# ZP_Force_Plates.net
KiCad netlist of a schematic drawn in Altium Designer
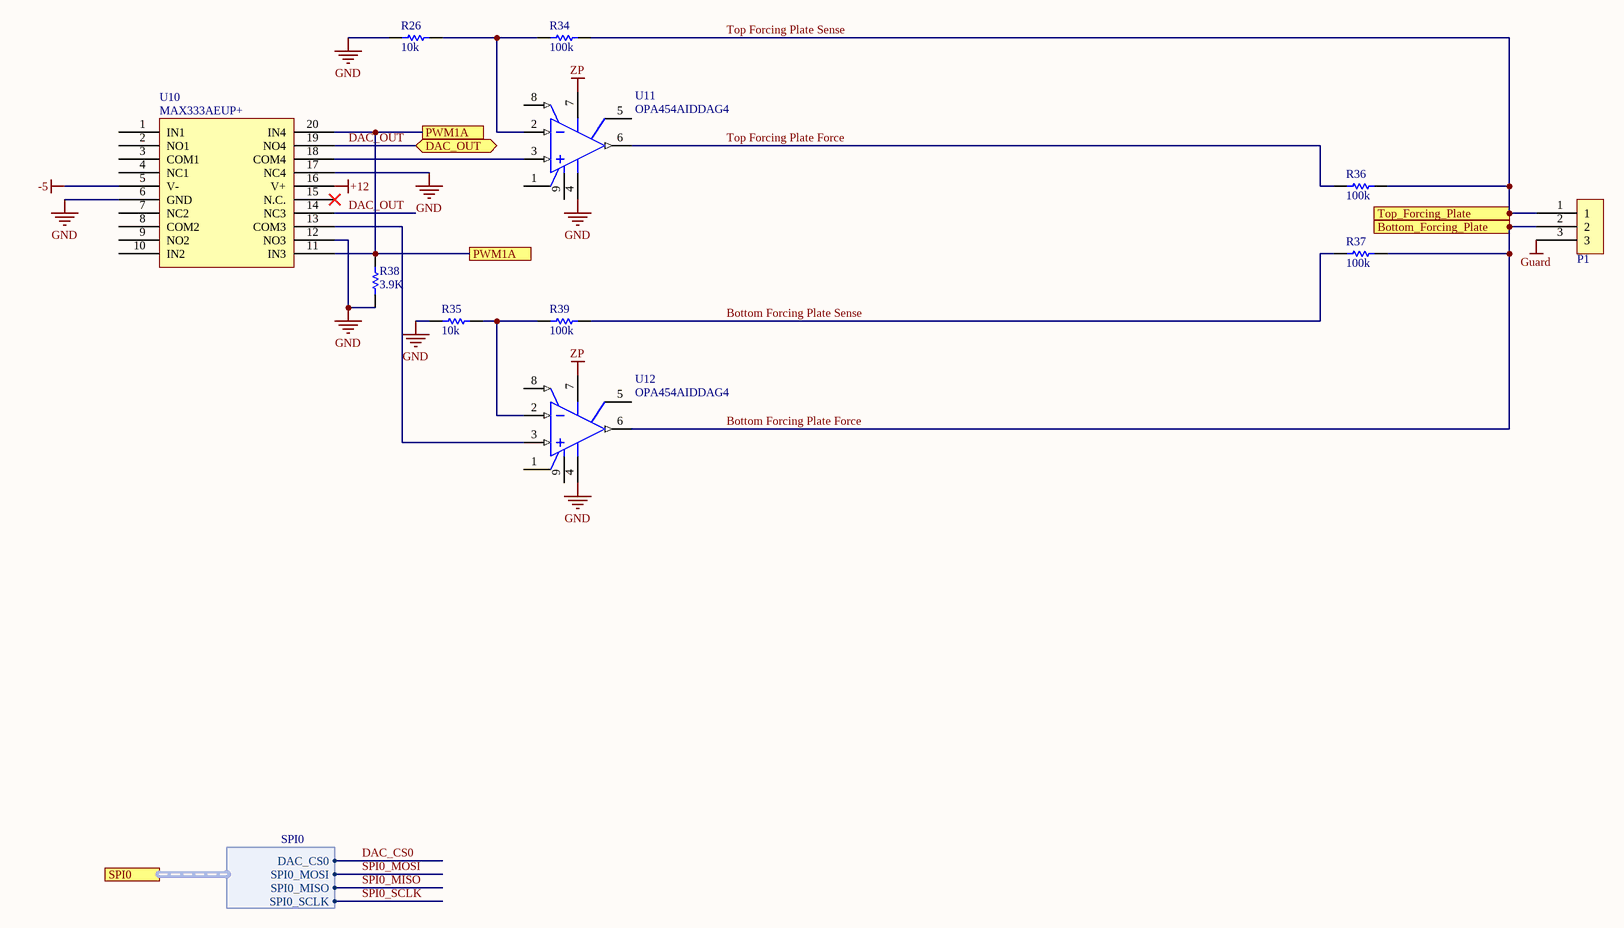
[diagram p0: ZP_Force_Plates.SchDoc]

(export (version "E")
  (design (tool "Eeschema 10.0.6"))
  (components
    (comp (ref "P1")
      (value "Triax_Conn")
      (footprint "Triax_Conn")
      (libsource (lib "ZLS_Schematic_lib") (part "Triax_Conn"))
    )
    (comp (ref "R26")
      (value "10k")
      (footprint "RESC0402(1005)_M")
      (libsource (lib "Altium Content Vault") (part "CMP-1011-00463-1"))
    )
    (comp (ref "R34")
      (value "100k")
      (footprint "RESC0402(1005)_M")
      (libsource (lib "Altium Content Vault") (part "CMP-1011-00463-1"))
    )
    (comp (ref "R35")
      (value "10k")
      (footprint "RESC0402(1005)_M")
      (libsource (lib "Altium Content Vault") (part "CMP-1011-00463-1"))
    )
    (comp (ref "R36")
      (value "100k")
      (footprint "RESC0402(1005)_M")
      (libsource (lib "Altium Content Vault") (part "CMP-1011-00651-1"))
    )
    (comp (ref "R37")
      (value "100k")
      (footprint "RESC0402(1005)_M")
      (libsource (lib "Altium Content Vault") (part "CMP-1011-00651-1"))
    )
    (comp (ref "R38")
      (value "3.9K")
      (footprint "RESC0402(1005)_M")
      (libsource (lib "Altium Content Vault") (part "CMP-1011-00463-1"))
    )
    (comp (ref "R39")
      (value "100k")
      (footprint "RESC0402(1005)_M")
      (libsource (lib "Altium Content Vault") (part "CMP-1011-00463-1"))
    )
    (comp (ref "U10")
      (value "MAX333AEUP+")
      (footprint "TSOP65P640X90-20N")
      (description "IC SWITCH QUAD SPDT 20TSSOP")
      (fields (field (name "MANUFACTURER") "Maxim Integrated") (field (name "BASE PART NUMBER") "MAX333"))
      (libsource (lib "ZLS_Schematic_lib") (part "MAX333CWP+"))
    )
    (comp (ref "U11")
      (value "OPA454AIDDAG4")
      (footprint "TI-DDA8-2745X2245TP_N")
      (fields (field (name "MANUFACTURER") "Texas Instruments"))
      (libsource (lib "Altium Content Vault") (part "TI-OPA454-DDA8"))
    )
    (comp (ref "U12")
      (value "OPA454AIDDAG4")
      (footprint "TI-DDA8-2745X2245TP_N")
      (fields (field (name "MANUFACTURER") "Texas Instruments"))
      (libsource (lib "Altium Content Vault") (part "TI-OPA454-DDA8"))
    )
  )
  (nets
    (net (code "2") (name "+12") (class "Default")
      (node (ref "U10") (pin "16") (pinfunction "V+_16") (pintype "power_in"))
    )
    (net (code "3") (name "-5") (class "Default")
      (node (ref "U10") (pin "5") (pinfunction "V-_5") (pintype "power_in"))
    )
    (net (code "4") (name "/Bottom Forcing Plate Force") (class "Default")
      (node (ref "P1") (pin "2") (pinfunction "2_2") (pintype "passive"))
      (node (ref "R37") (pin "1") (pinfunction "1_1") (pintype "passive"))
      (node (ref "U12") (pin "6") (pinfunction "OUT_6") (pintype "output"))
    )
    (net (code "5") (name "/Bottom Forcing Plate Sense") (class "Default")
      (node (ref "R37") (pin "2") (pinfunction "2_2") (pintype "passive"))
      (node (ref "R39") (pin "2") (pinfunction "2_2") (pintype "passive"))
    )
    (net (code "7") (name "/DAC_OUT") (class "Default")
      (node (ref "U10") (pin "14") (pinfunction "NC3_14") (pintype "passive"))
      (node (ref "U10") (pin "19") (pinfunction "NO4_19") (pintype "passive"))
    )
    (net (code "8") (name "/PWM1A") (class "Default")
      (node (ref "R38") (pin "2") (pinfunction "2_2") (pintype "passive"))
      (node (ref "U10") (pin "11") (pinfunction "IN3_11") (pintype "passive"))
      (node (ref "U10") (pin "20") (pinfunction "IN4_20") (pintype "passive"))
    )
    (net (code "12") (name "/Top Forcing Plate Force") (class "Default")
      (node (ref "R36") (pin "2") (pinfunction "2_2") (pintype "passive"))
      (node (ref "U11") (pin "6") (pinfunction "OUT_6") (pintype "output"))
    )
    (net (code "13") (name "/Top Forcing Plate Sense") (class "Default")
      (node (ref "P1") (pin "1") (pinfunction "1_1") (pintype "passive"))
      (node (ref "R34") (pin "2") (pinfunction "2_2") (pintype "passive"))
      (node (ref "R36") (pin "1") (pinfunction "1_1") (pintype "passive"))
    )
    (net (code "15") (name "GND") (class "Default")
      (node (ref "R26") (pin "1") (pinfunction "1_1") (pintype "passive"))
      (node (ref "R35") (pin "1") (pinfunction "1_1") (pintype "passive"))
      (node (ref "R38") (pin "1") (pinfunction "1_1") (pintype "passive"))
      (node (ref "U10") (pin "12") (pinfunction "NO3_12") (pintype "passive"))
      (node (ref "U10") (pin "17") (pinfunction "NC4_17") (pintype "passive"))
      (node (ref "U10") (pin "6") (pinfunction "GND_6") (pintype "passive"))
      (node (ref "U11") (pin "4") (pinfunction "V-_4") (pintype "power_in"))
      (node (ref "U12") (pin "4") (pinfunction "V-_4") (pintype "power_in"))
    )
    (net (code "16") (name "Guard") (class "Default")
      (node (ref "P1") (pin "3") (pinfunction "3_3") (pintype "passive"))
    )
    (net (code "17") (name "Net-(U10-COM3)") (class "Default")
      (node (ref "U10") (pin "13") (pinfunction "COM3_13") (pintype "passive"))
      (node (ref "U12") (pin "3") (pinfunction "IN+_3") (pintype "input"))
    )
    (net (code "18") (name "Net-(U10-COM4)") (class "Default")
      (node (ref "U10") (pin "18") (pinfunction "COM4_18") (pintype "passive"))
      (node (ref "U11") (pin "3") (pinfunction "IN+_3") (pintype "input"))
    )
    (net (code "19") (name "Net-(U11-IN-)") (class "Default")
      (node (ref "R26") (pin "2") (pinfunction "2_2") (pintype "passive"))
      (node (ref "R34") (pin "1") (pinfunction "1_1") (pintype "passive"))
      (node (ref "U11") (pin "2") (pinfunction "IN-_2") (pintype "input"))
    )
    (net (code "20") (name "Net-(U12-IN-)") (class "Default")
      (node (ref "R35") (pin "2") (pinfunction "2_2") (pintype "passive"))
      (node (ref "R39") (pin "1") (pinfunction "1_1") (pintype "passive"))
      (node (ref "U12") (pin "2") (pinfunction "IN-_2") (pintype "input"))
    )
    (net (code "21") (name "ZP") (class "Default")
      (node (ref "U11") (pin "7") (pinfunction "V+_7") (pintype "power_in"))
      (node (ref "U12") (pin "7") (pinfunction "V+_7") (pintype "power_in"))
    )
    (net (code "22") (name "unconnected-(U10-COM1-Pad3)") (class "Default")
      (node (ref "U10") (pin "3") (pinfunction "COM1_3") (pintype "passive"))
    )
    (net (code "23") (name "unconnected-(U10-COM2-Pad8)") (class "Default")
      (node (ref "U10") (pin "8") (pinfunction "COM2_8") (pintype "passive"))
    )
    (net (code "24") (name "unconnected-(U10-IN1-Pad1)") (class "Default")
      (node (ref "U10") (pin "1") (pinfunction "IN1_1") (pintype "passive"))
    )
    (net (code "25") (name "unconnected-(U10-IN2-Pad10)") (class "Default")
      (node (ref "U10") (pin "10") (pinfunction "IN2_10") (pintype "passive"))
    )
    (net (code "26") (name "unconnected-(U10-N.C.-Pad15)") (class "Default")
      (node (ref "U10") (pin "15") (pinfunction "N.C._15") (pintype "passive+no_connect"))
    )
    (net (code "27") (name "unconnected-(U10-NC1-Pad4)") (class "Default")
      (node (ref "U10") (pin "4") (pinfunction "NC1_4") (pintype "passive"))
    )
    (net (code "28") (name "unconnected-(U10-NC2-Pad7)") (class "Default")
      (node (ref "U10") (pin "7") (pinfunction "NC2_7") (pintype "passive"))
    )
    (net (code "29") (name "unconnected-(U10-NO1-Pad2)") (class "Default")
      (node (ref "U10") (pin "2") (pinfunction "NO1_2") (pintype "passive"))
    )
    (net (code "30") (name "unconnected-(U10-NO2-Pad9)") (class "Default")
      (node (ref "U10") (pin "9") (pinfunction "NO2_9") (pintype "passive"))
    )
    (net (code "31") (name "unconnected-(U11-EP-Pad9)") (class "Default")
      (node (ref "U11") (pin "9") (pinfunction "EP_9") (pintype "power_in"))
    )
    (net (code "32") (name "unconnected-(U11-E{slash}D-Pad8)") (class "Default")
      (node (ref "U11") (pin "8") (pinfunction "E/D_8") (pintype "input"))
    )
    (net (code "33") (name "unconnected-(U11-E{slash}D_COM-Pad1)") (class "Default")
      (node (ref "U11") (pin "1") (pinfunction "E/D_COM_1") (pintype "power_in"))
    )
    (net (code "34") (name "unconnected-(U11-STATUS_FLAG-Pad5)") (class "Default")
      (node (ref "U11") (pin "5") (pinfunction "STATUS_FLAG_5") (pintype "open_collector"))
    )
    (net (code "35") (name "unconnected-(U12-EP-Pad9)") (class "Default")
      (node (ref "U12") (pin "9") (pinfunction "EP_9") (pintype "power_in"))
    )
    (net (code "36") (name "unconnected-(U12-E{slash}D-Pad8)") (class "Default")
      (node (ref "U12") (pin "8") (pinfunction "E/D_8") (pintype "input"))
    )
    (net (code "37") (name "unconnected-(U12-E{slash}D_COM-Pad1)") (class "Default")
      (node (ref "U12") (pin "1") (pinfunction "E/D_COM_1") (pintype "power_in"))
    )
    (net (code "38") (name "unconnected-(U12-STATUS_FLAG-Pad5)") (class "Default")
      (node (ref "U12") (pin "5") (pinfunction "STATUS_FLAG_5") (pintype "open_collector"))
    )
  )
)
